# TRANSMITTER.net
KiCad netlist of a schematic drawn in Altium Designer
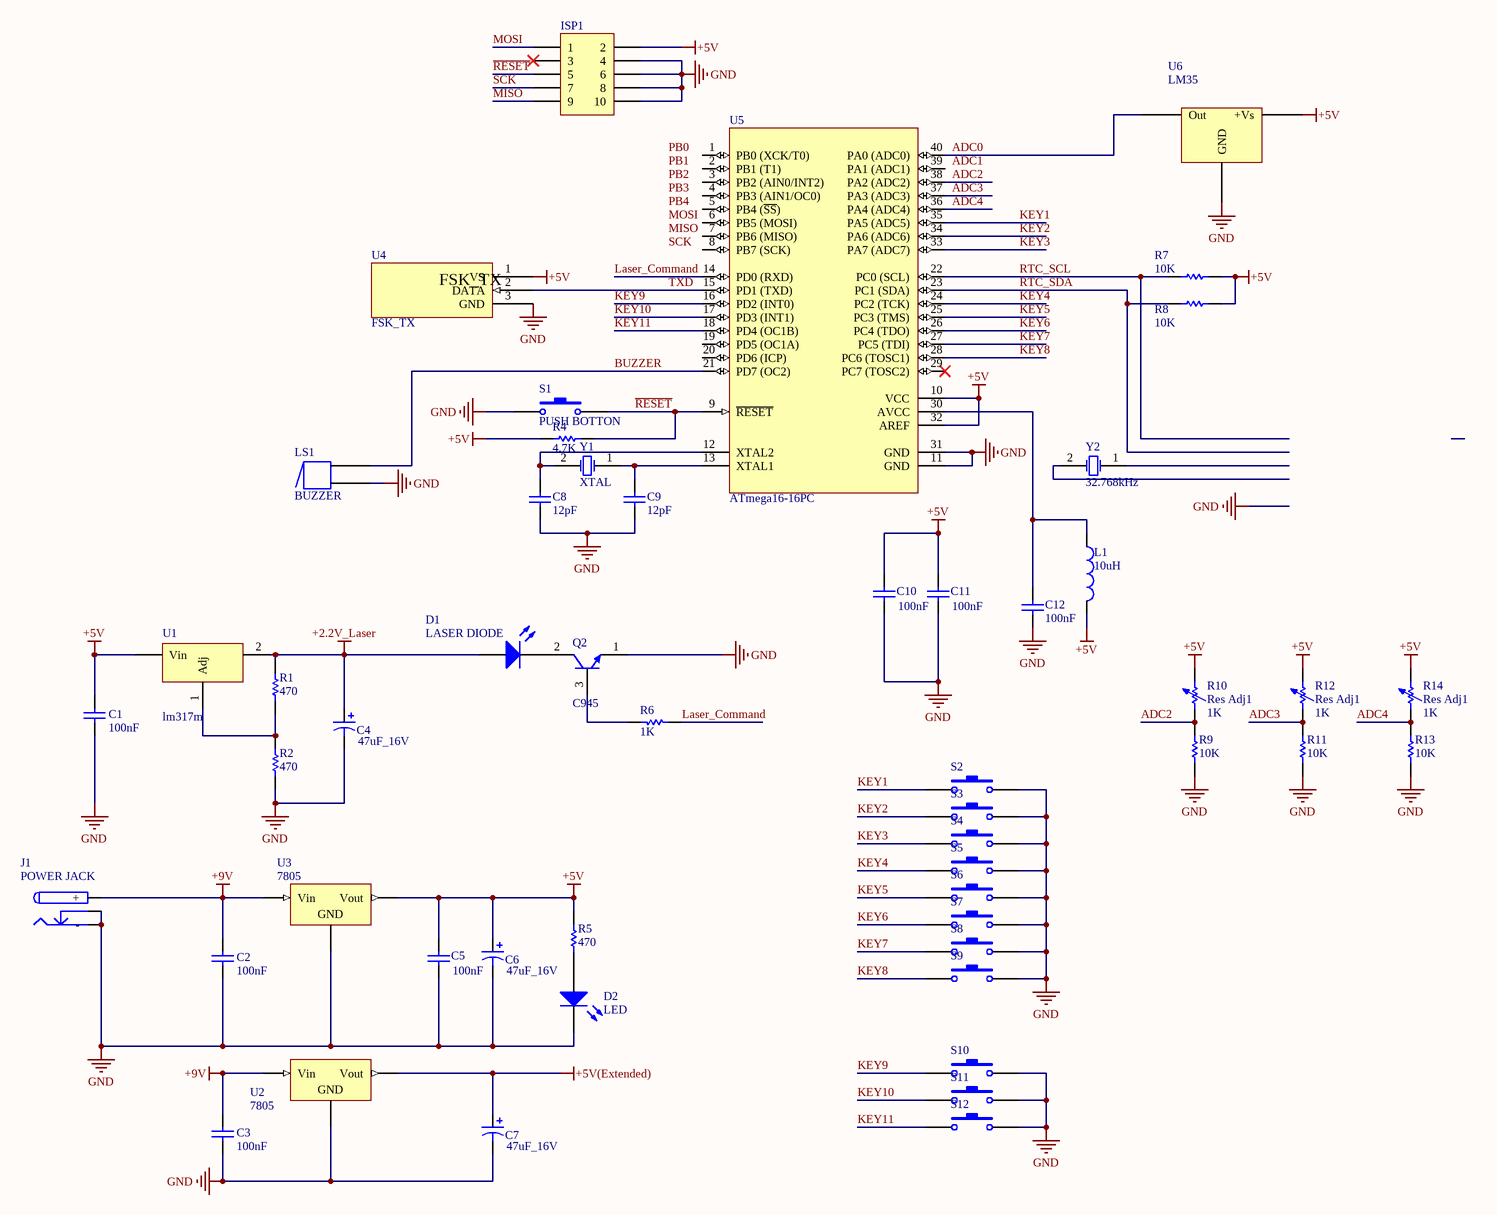
[diagram p0: TRANSMITTER.SchDoc]

(export (version "E")
  (design (tool "Eeschema 10.0.6"))
  (components
    (comp (ref "C1") (value "100nF") (footprint "BCY-W2/D3.1") (libsource (lib "SCHlib") (part "CAP")))
    (comp (ref "C2") (value "100nF") (footprint "BCY-W2/D3.1") (libsource (lib "SCHlib") (part "CAP")))
    (comp (ref "C3") (value "100nF") (footprint "BCY-W2/D3.1") (libsource (lib "SCHlib") (part "CAP")))
    (comp (ref "C4")
      (value "47uF_16V")
      (footprint "cap_pol")
      (fields (field (name "Comment") "CAP_POL"))
      (libsource (lib "SCHlib") (part "CAP_POL"))
    )
    (comp (ref "C5") (value "100nF") (footprint "BCY-W2/D3.1") (libsource (lib "SCHlib") (part "CAP")))
    (comp (ref "C6")
      (value "47uF_16V")
      (footprint "cap_pol")
      (fields (field (name "Comment") "CAP_POL"))
      (libsource (lib "SCHlib") (part "CAP_POL"))
    )
    (comp (ref "C7")
      (value "47uF_16V")
      (footprint "cap_pol")
      (fields (field (name "Comment") "CAP_POL"))
      (libsource (lib "SCHlib") (part "CAP_POL"))
    )
    (comp (ref "C8") (value "12pF") (footprint "BCY-W2/D3.1") (libsource (lib "SCHlib") (part "CAP")))
    (comp (ref "C9") (value "12pF") (footprint "BCY-W2/D3.1") (libsource (lib "SCHlib") (part "CAP")))
    (comp (ref "C10") (value "100nF") (footprint "BCY-W2/D3.1") (libsource (lib "SCHlib") (part "CAP")))
    (comp (ref "C11") (value "100nF") (footprint "BCY-W2/D3.1") (libsource (lib "SCHlib") (part "CAP")))
    (comp (ref "C12")
      (value "100nF")
      (footprint "BCY-W2/D3.1")
      (description "Capacitor (Semiconductor SIM Model)")
      (fields (field (name "PUBLISHER") "Altium Limited"))
      (libsource (lib "Miscellaneous Devices") (part "Cap Semi"))
    )
    (comp (ref "D1") (value "LASER DIODE") (footprint "Com_2pin") (libsource (lib "SCHlib") (part "LED")))
    (comp (ref "D2") (value "LED") (footprint "LED_3mm") (libsource (lib "SCHlib") (part "LED")))
    (comp (ref "ISP1")
      (value "ISP Programmer")
      (footprint "IDC2*5")
      (description "Header, 5-Pin, Dual row")
      (fields (field (name "PUBLISHER") "Altium Limited"))
      (libsource (lib "Miscellaneous Connectors") (part "Header 5X2"))
    )
    (comp (ref "J1") (value "POWER JACK") (footprint "term2") (libsource (lib "SCHlib") (part "POWER JACK")))
    (comp (ref "L1")
      (value "10uH")
      (footprint "AXIAL0.3")
      (description "Inductor")
      (fields (field (name "PUBLISHER") "Altium Limited"))
      (libsource (lib "SCH_lib") (part "Inductor"))
    )
    (comp (ref "LS1")
      (value "BUZZER")
      (footprint "buzzer")
      (description "Magnetic Transducer Buzzer")
      (libsource (lib "SCHlib") (part "BUZZER"))
    )
    (comp (ref "Q2")
      (value "C945")
      (footprint "C945")
      (description "NPN Bipolar Junction Transistor")
      (libsource (lib "SCHlib") (part "C945"))
    )
    (comp (ref "R1") (value "470") (footprint "AXIAL0.4") (libsource (lib "SCHlib") (part "RES")))
    (comp (ref "R2") (value "470") (footprint "AXIAL0.4") (libsource (lib "SCHlib") (part "RES")))
    (comp (ref "R4") (value "4.7K") (footprint "AXIAL0.4") (libsource (lib "SCHlib") (part "RES")))
    (comp (ref "R5") (value "470") (footprint "AXIAL0.4") (libsource (lib "SCHlib") (part "RES")))
    (comp (ref "R6") (value "1K") (footprint "AXIAL0.4") (libsource (lib "") (part "RES_1")))
    (comp (ref "R7") (value "10K") (footprint "AXIAL0.4") (libsource (lib "SCHlib") (part "RES")))
    (comp (ref "R8") (value "10K") (footprint "AXIAL0.4") (libsource (lib "SCHlib") (part "RES")))
    (comp (ref "R9") (value "10K") (footprint "AXIAL0.4") (libsource (lib "SCHlib") (part "RES")))
    (comp (ref "R10")
      (value "Res Adj1")
      (footprint "Com_2pin")
      (description "Variable Resistor")
      (fields (field (name "ALTIUM_VALUE") "1K") (field (name "PUBLISHER") "Altium Limited"))
      (libsource (lib "Miscellaneous Devices") (part "Res Adj1"))
    )
    (comp (ref "R11") (value "10K") (footprint "AXIAL0.4") (libsource (lib "SCHlib") (part "RES")))
    (comp (ref "R12")
      (value "Res Adj1")
      (footprint "Com_2pin")
      (description "Variable Resistor")
      (fields (field (name "ALTIUM_VALUE") "1K") (field (name "PUBLISHER") "Altium Limited"))
      (libsource (lib "Miscellaneous Devices") (part "Res Adj1"))
    )
    (comp (ref "R13") (value "10K") (footprint "AXIAL0.4") (libsource (lib "SCHlib") (part "RES")))
    (comp (ref "R14")
      (value "Res Adj1")
      (footprint "Com_2pin")
      (description "Variable Resistor")
      (fields (field (name "ALTIUM_VALUE") "1K") (field (name "PUBLISHER") "Altium Limited"))
      (libsource (lib "Miscellaneous Devices") (part "Res Adj1"))
    )
    (comp (ref "S1")
      (value "PUSH BOTTON")
      (footprint "PUSH BUTTON")
      (libsource (lib "SCHlib") (part "PUSH BOTTON"))
    )
    (comp (ref "S2")
      (value "PUSH BOTTON")
      (footprint "PUSH BUTTON")
      (libsource (lib "SCHlib") (part "PUSH BOTTON"))
    )
    (comp (ref "S3")
      (value "PUSH BOTTON")
      (footprint "PUSH BUTTON")
      (libsource (lib "SCHlib") (part "PUSH BOTTON"))
    )
    (comp (ref "S4")
      (value "PUSH BOTTON")
      (footprint "PUSH BUTTON")
      (libsource (lib "SCHlib") (part "PUSH BOTTON"))
    )
    (comp (ref "S5")
      (value "PUSH BOTTON")
      (footprint "PUSH BUTTON")
      (libsource (lib "SCHlib") (part "PUSH BOTTON"))
    )
    (comp (ref "S6")
      (value "PUSH BOTTON")
      (footprint "PUSH BUTTON")
      (libsource (lib "SCHlib") (part "PUSH BOTTON"))
    )
    (comp (ref "S7")
      (value "PUSH BOTTON")
      (footprint "PUSH BUTTON")
      (libsource (lib "SCHlib") (part "PUSH BOTTON"))
    )
    (comp (ref "S8")
      (value "PUSH BOTTON")
      (footprint "PUSH BUTTON")
      (libsource (lib "SCHlib") (part "PUSH BOTTON"))
    )
    (comp (ref "S9")
      (value "PUSH BOTTON")
      (footprint "PUSH BUTTON")
      (libsource (lib "SCHlib") (part "PUSH BOTTON"))
    )
    (comp (ref "S10")
      (value "PUSH BOTTON")
      (footprint "PUSH BUTTON")
      (libsource (lib "SCHlib") (part "PUSH BOTTON"))
    )
    (comp (ref "S11")
      (value "PUSH BOTTON")
      (footprint "PUSH BUTTON")
      (libsource (lib "SCHlib") (part "PUSH BOTTON"))
    )
    (comp (ref "S12")
      (value "PUSH BOTTON")
      (footprint "PUSH BUTTON")
      (libsource (lib "SCHlib") (part "PUSH BOTTON"))
    )
    (comp (ref "U1") (value "lm317m") (footprint "17D") (libsource (lib "RobotComponents") (part "lm317m")))
    (comp (ref "U2") (value "7805") (footprint "7805") (libsource (lib "SCHlib") (part "7805")))
    (comp (ref "U3") (value "7805") (footprint "7805") (libsource (lib "SCHlib") (part "7805")))
    (comp (ref "U4") (value "FSK_TX") (footprint "FSK_TX") (libsource (lib "SCHlib") (part "FSK_TX")))
    (comp (ref "U5")
      (value "ATmega16-16PC")
      (footprint "40P6")
      (description "8-Bit AVR Microcontroller with 16K Bytes of In-System Programmable Flash Memory")
      (fields (field (name "PUBLISHER") "Altium Limited"))
      (libsource (lib "SCHlib") (part "ATmega16-16PC"))
    )
    (comp (ref "U6") (value "LM35") (footprint "C945") (libsource (lib "RobotComponents") (part "LM35")))
    (comp (ref "Y1")
      (value "XTAL")
      (footprint "XTAL")
      (description "Crystal Oscillator")
      (fields (field (name "PUBLISHER") "Altium Limited"))
      (libsource (lib "SCHlib") (part "XTAL"))
    )
    (comp (ref "Y2")
      (value "32.768kHz")
      (footprint "R145")
      (description "Crystal Oscillator")
      (fields (field (name "PUBLISHER") "Altium Limited"))
      (libsource (lib "Miscellaneous Devices") (part "XTAL"))
    )
  )
  (nets
    (net (code "1") (name "+2.2V_Laser") (class "Default")
      (node (ref "C4") (pin "1") (pinfunction "1_1") (pintype "passive"))
      (node (ref "D1") (pin "1") (pinfunction "A_1") (pintype "passive"))
      (node (ref "R1") (pin "1") (pinfunction "1_1") (pintype "passive"))
      (node (ref "U1") (pin "2") (pinfunction "Vout_2") (pintype "passive"))
    )
    (net (code "2") (name "+5V") (class "Default")
      (node (ref "C1") (pin "2") (pinfunction "2_2") (pintype "passive"))
      (node (ref "C10") (pin "2") (pinfunction "2_2") (pintype "passive"))
      (node (ref "C11") (pin "2") (pinfunction "2_2") (pintype "passive"))
      (node (ref "C5") (pin "2") (pinfunction "2_2") (pintype "passive"))
      (node (ref "C6") (pin "1") (pinfunction "1_1") (pintype "passive"))
      (node (ref "ISP1") (pin "2") (pinfunction "2_2") (pintype "passive"))
      (node (ref "L1") (pin "2") (pinfunction "2_2") (pintype "passive"))
      (node (ref "R10") (pin "2") (pinfunction "2_2") (pintype "passive"))
      (node (ref "R12") (pin "2") (pinfunction "2_2") (pintype "passive"))
      (node (ref "R14") (pin "2") (pinfunction "2_2") (pintype "passive"))
      (node (ref "R4") (pin "2") (pinfunction "2_2") (pintype "passive"))
      (node (ref "R5") (pin "1") (pinfunction "1_1") (pintype "passive"))
      (node (ref "R7") (pin "2") (pinfunction "2_2") (pintype "passive"))
      (node (ref "R8") (pin "1") (pinfunction "1_1") (pintype "passive"))
      (node (ref "U1") (pin "3") (pinfunction "Vin_3") (pintype "passive"))
      (node (ref "U3") (pin "3") (pinfunction "Vout_3") (pintype "output"))
      (node (ref "U4") (pin "1") (pinfunction "VS_1") (pintype "power_in"))
      (node (ref "U5") (pin "10") (pinfunction "VCC_10") (pintype "power_in"))
      (node (ref "U5") (pin "32") (pinfunction "AREF_32") (pintype "passive"))
      (node (ref "U6") (pin "1") (pinfunction "+Vs_1") (pintype "passive"))
    )
    (net (code "3") (name "+5V(Extended)") (class "Default")
      (node (ref "C7") (pin "1") (pinfunction "1_1") (pintype "passive"))
      (node (ref "U2") (pin "3") (pinfunction "Vout_3") (pintype "output"))
    )
    (net (code "4") (name "+9V") (class "Default")
      (node (ref "C2") (pin "2") (pinfunction "2_2") (pintype "passive"))
      (node (ref "C3") (pin "2") (pinfunction "2_2") (pintype "passive"))
      (node (ref "J1") (pin "1") (pinfunction "+_1") (pintype "power_in"))
      (node (ref "U2") (pin "1") (pinfunction "Vin_1") (pintype "input"))
      (node (ref "U3") (pin "1") (pinfunction "Vin_1") (pintype "input"))
    )
    (net (code "5") (name "/ADC0") (class "Default")
      (node (ref "U5") (pin "40") (pinfunction "PA0_(ADC0)_40") (pintype "bidirectional"))
      (node (ref "U6") (pin "2") (pinfunction "Out_2") (pintype "passive"))
    )
    (net (code "7") (name "/ADC2") (class "Default")
      (node (ref "R10") (pin "1") (pinfunction "1_1") (pintype "passive"))
      (node (ref "R9") (pin "2") (pinfunction "2_2") (pintype "passive"))
      (node (ref "U5") (pin "38") (pinfunction "PA2_(ADC2)_38") (pintype "bidirectional"))
    )
    (net (code "8") (name "/ADC3") (class "Default")
      (node (ref "R11") (pin "2") (pinfunction "2_2") (pintype "passive"))
      (node (ref "R12") (pin "1") (pinfunction "1_1") (pintype "passive"))
      (node (ref "U5") (pin "37") (pinfunction "PA3_(ADC3)_37") (pintype "bidirectional"))
    )
    (net (code "9") (name "/ADC4") (class "Default")
      (node (ref "R13") (pin "2") (pinfunction "2_2") (pintype "passive"))
      (node (ref "R14") (pin "1") (pinfunction "1_1") (pintype "passive"))
      (node (ref "U5") (pin "36") (pinfunction "PA4_(ADC4)_36") (pintype "bidirectional"))
    )
    (net (code "10") (name "/BUZZER") (class "Default")
      (node (ref "LS1") (pin "1") (pinfunction "1_1") (pintype "passive"))
      (node (ref "U5") (pin "21") (pinfunction "PD7_(OC2)_21") (pintype "bidirectional"))
    )
    (net (code "11") (name "/KEY1") (class "Default")
      (node (ref "S2") (pin "1") (pinfunction "1_1") (pintype "passive"))
      (node (ref "U5") (pin "35") (pinfunction "PA5_(ADC5)_35") (pintype "bidirectional"))
    )
    (net (code "12") (name "/KEY2") (class "Default")
      (node (ref "S3") (pin "1") (pinfunction "1_1") (pintype "passive"))
      (node (ref "U5") (pin "34") (pinfunction "PA6_(ADC6)_34") (pintype "bidirectional"))
    )
    (net (code "13") (name "/KEY3") (class "Default")
      (node (ref "S4") (pin "1") (pinfunction "1_1") (pintype "passive"))
      (node (ref "U5") (pin "33") (pinfunction "PA7_(ADC7)_33") (pintype "bidirectional"))
    )
    (net (code "14") (name "/KEY4") (class "Default")
      (node (ref "S5") (pin "1") (pinfunction "1_1") (pintype "passive"))
      (node (ref "U5") (pin "24") (pinfunction "PC2_(TCK)_24") (pintype "bidirectional"))
    )
    (net (code "15") (name "/KEY5") (class "Default")
      (node (ref "S6") (pin "1") (pinfunction "1_1") (pintype "passive"))
      (node (ref "U5") (pin "25") (pinfunction "PC3_(TMS)_25") (pintype "bidirectional"))
    )
    (net (code "16") (name "/KEY6") (class "Default")
      (node (ref "S7") (pin "1") (pinfunction "1_1") (pintype "passive"))
      (node (ref "U5") (pin "26") (pinfunction "PC4_(TDO)_26") (pintype "bidirectional"))
    )
    (net (code "17") (name "/KEY7") (class "Default")
      (node (ref "S8") (pin "1") (pinfunction "1_1") (pintype "passive"))
      (node (ref "U5") (pin "27") (pinfunction "PC5_(TDI)_27") (pintype "bidirectional"))
    )
    (net (code "18") (name "/KEY8") (class "Default")
      (node (ref "S9") (pin "1") (pinfunction "1_1") (pintype "passive"))
      (node (ref "U5") (pin "28") (pinfunction "PC6_(TOSC1)_28") (pintype "bidirectional"))
    )
    (net (code "19") (name "/KEY9") (class "Default")
      (node (ref "S10") (pin "1") (pinfunction "1_1") (pintype "passive"))
      (node (ref "U5") (pin "16") (pinfunction "PD2_(INT0)_16") (pintype "bidirectional"))
    )
    (net (code "20") (name "/KEY10") (class "Default")
      (node (ref "S11") (pin "1") (pinfunction "1_1") (pintype "passive"))
      (node (ref "U5") (pin "17") (pinfunction "PD3_(INT1)_17") (pintype "bidirectional"))
    )
    (net (code "21") (name "/KEY11") (class "Default")
      (node (ref "S12") (pin "1") (pinfunction "1_1") (pintype "passive"))
      (node (ref "U5") (pin "18") (pinfunction "PD4_(OC1B)_18") (pintype "bidirectional"))
    )
    (net (code "22") (name "/Laser_Command") (class "Default")
      (node (ref "R6") (pin "1") (pinfunction "1_1") (pintype "passive"))
      (node (ref "U5") (pin "14") (pinfunction "PD0_(RXD)_14") (pintype "bidirectional"))
    )
    (net (code "23") (name "/MISO") (class "Default")
      (node (ref "ISP1") (pin "9") (pinfunction "9_9") (pintype "passive"))
    )
    (net (code "24") (name "/MOSI") (class "Default")
      (node (ref "ISP1") (pin "1") (pinfunction "1_1") (pintype "passive"))
    )
    (net (code "30") (name "/RTC_SCL") (class "Default")
      (node (ref "R7") (pin "1") (pinfunction "1_1") (pintype "passive"))
      (node (ref "U5") (pin "22") (pinfunction "PC0_(SCL)_22") (pintype "bidirectional"))
    )
    (net (code "31") (name "/RTC_SDA") (class "Default")
      (node (ref "R8") (pin "2") (pinfunction "2_2") (pintype "passive"))
      (node (ref "U5") (pin "23") (pinfunction "PC1_(SDA)_23") (pintype "bidirectional"))
    )
    (net (code "32") (name "/SCK") (class "Default")
      (node (ref "ISP1") (pin "7") (pinfunction "7_7") (pintype "passive"))
    )
    (net (code "33") (name "/TXD") (class "Default")
      (node (ref "U4") (pin "2") (pinfunction "DATA_2") (pintype "input"))
      (node (ref "U5") (pin "15") (pinfunction "PD1_(TXD)_15") (pintype "bidirectional"))
    )
    (net (code "34") (name "/~{RESET}") (class "Default")
      (node (ref "ISP1") (pin "5") (pinfunction "5_5") (pintype "passive"))
      (node (ref "R4") (pin "1") (pinfunction "1_1") (pintype "passive"))
      (node (ref "S1") (pin "2") (pinfunction "2_2") (pintype "passive"))
      (node (ref "U5") (pin "9") (pinfunction "~{RESET}_9") (pintype "input"))
    )
    (net (code "35") (name "GND") (class "Default")
      (node (ref "C1") (pin "1") (pinfunction "1_1") (pintype "passive"))
      (node (ref "C10") (pin "1") (pinfunction "1_1") (pintype "passive"))
      (node (ref "C11") (pin "1") (pinfunction "1_1") (pintype "passive"))
      (node (ref "C12") (pin "1") (pinfunction "1_1") (pintype "passive"))
      (node (ref "C2") (pin "1") (pinfunction "1_1") (pintype "passive"))
      (node (ref "C3") (pin "1") (pinfunction "1_1") (pintype "passive"))
      (node (ref "C4") (pin "2") (pinfunction "2_2") (pintype "passive"))
      (node (ref "C5") (pin "1") (pinfunction "1_1") (pintype "passive"))
      (node (ref "C6") (pin "2") (pinfunction "2_2") (pintype "passive"))
      (node (ref "C7") (pin "2") (pinfunction "2_2") (pintype "passive"))
      (node (ref "C8") (pin "1") (pinfunction "1_1") (pintype "passive"))
      (node (ref "C9") (pin "1") (pinfunction "1_1") (pintype "passive"))
      (node (ref "D2") (pin "2") (pinfunction "K_2") (pintype "passive"))
      (node (ref "ISP1") (pin "10") (pinfunction "10_10") (pintype "passive"))
      (node (ref "ISP1") (pin "4") (pinfunction "4_4") (pintype "passive"))
      (node (ref "ISP1") (pin "6") (pinfunction "6_6") (pintype "passive"))
      (node (ref "ISP1") (pin "8") (pinfunction "8_8") (pintype "passive"))
      (node (ref "J1") (pin "2") (pinfunction "-_2") (pintype "power_in"))
      (node (ref "LS1") (pin "2") (pinfunction "2_2") (pintype "passive"))
      (node (ref "Q2") (pin "1") (pinfunction "E_1") (pintype "passive"))
      (node (ref "R11") (pin "1") (pinfunction "1_1") (pintype "passive"))
      (node (ref "R13") (pin "1") (pinfunction "1_1") (pintype "passive"))
      (node (ref "R2") (pin "2") (pinfunction "2_2") (pintype "passive"))
      (node (ref "R9") (pin "1") (pinfunction "1_1") (pintype "passive"))
      (node (ref "S1") (pin "1") (pinfunction "1_1") (pintype "passive"))
      (node (ref "S10") (pin "2") (pinfunction "2_2") (pintype "passive"))
      (node (ref "S11") (pin "2") (pinfunction "2_2") (pintype "passive"))
      (node (ref "S12") (pin "2") (pinfunction "2_2") (pintype "passive"))
      (node (ref "S2") (pin "2") (pinfunction "2_2") (pintype "passive"))
      (node (ref "S3") (pin "2") (pinfunction "2_2") (pintype "passive"))
      (node (ref "S4") (pin "2") (pinfunction "2_2") (pintype "passive"))
      (node (ref "S5") (pin "2") (pinfunction "2_2") (pintype "passive"))
      (node (ref "S6") (pin "2") (pinfunction "2_2") (pintype "passive"))
      (node (ref "S7") (pin "2") (pinfunction "2_2") (pintype "passive"))
      (node (ref "S8") (pin "2") (pinfunction "2_2") (pintype "passive"))
      (node (ref "S9") (pin "2") (pinfunction "2_2") (pintype "passive"))
      (node (ref "U2") (pin "2") (pinfunction "GND_2") (pintype "power_in"))
      (node (ref "U3") (pin "2") (pinfunction "GND_2") (pintype "power_in"))
      (node (ref "U4") (pin "3") (pinfunction "GND_3") (pintype "power_in"))
      (node (ref "U5") (pin "11") (pinfunction "GND_11") (pintype "power_in"))
      (node (ref "U5") (pin "31") (pinfunction "GND_31") (pintype "power_in"))
      (node (ref "U6") (pin "3") (pinfunction "GND_3") (pintype "passive"))
    )
    (net (code "36") (name "Net-(D1-K)") (class "Default")
      (node (ref "D1") (pin "2") (pinfunction "K_2") (pintype "passive"))
      (node (ref "Q2") (pin "2") (pinfunction "C_2") (pintype "passive"))
    )
    (net (code "37") (name "Net-(D2-A)") (class "Default")
      (node (ref "D2") (pin "1") (pinfunction "A_1") (pintype "passive"))
      (node (ref "R5") (pin "2") (pinfunction "2_2") (pintype "passive"))
    )
    (net (code "38") (name "Net-(Q2-B)") (class "Default")
      (node (ref "Q2") (pin "3") (pinfunction "B_3") (pintype "passive"))
      (node (ref "R6") (pin "2") (pinfunction "2_2") (pintype "passive"))
    )
    (net (code "39") (name "Net-(U1-Adj)") (class "Default")
      (node (ref "R1") (pin "2") (pinfunction "2_2") (pintype "passive"))
      (node (ref "R2") (pin "1") (pinfunction "1_1") (pintype "passive"))
      (node (ref "U1") (pin "1") (pinfunction "Adj_1") (pintype "passive"))
    )
    (net (code "40") (name "Net-(U5-AVCC)") (class "Default")
      (node (ref "C12") (pin "2") (pinfunction "2_2") (pintype "passive"))
      (node (ref "L1") (pin "1") (pinfunction "1_1") (pintype "passive"))
      (node (ref "U5") (pin "30") (pinfunction "AVCC_30") (pintype "power_in"))
    )
    (net (code "41") (name "Net-(U5-XTAL1)") (class "Default")
      (node (ref "C9") (pin "2") (pinfunction "2_2") (pintype "passive"))
      (node (ref "U5") (pin "13") (pinfunction "XTAL1_13") (pintype "passive"))
      (node (ref "Y1") (pin "1") (pinfunction "OSC1_1") (pintype "passive"))
    )
    (net (code "42") (name "Net-(U5-XTAL2)") (class "Default")
      (node (ref "C8") (pin "2") (pinfunction "2_2") (pintype "passive"))
      (node (ref "U5") (pin "12") (pinfunction "XTAL2_12") (pintype "passive"))
      (node (ref "Y1") (pin "2") (pinfunction "OSC2_2") (pintype "passive"))
    )
    (net (code "43") (name "unconnected-(ISP1-Pad3)") (class "Default")
      (node (ref "ISP1") (pin "3") (pinfunction "3_3") (pintype "passive+no_connect"))
    )
    (net (code "44") (name "unconnected-(U5-PA1_(ADC1)-Pad39)") (class "Default")
      (node (ref "U5") (pin "39") (pinfunction "PA1_(ADC1)_39") (pintype "bidirectional"))
    )
    (net (code "45") (name "unconnected-(U5-PB0_(XCK{slash}T0)-Pad1)") (class "Default")
      (node (ref "U5") (pin "1") (pinfunction "PB0_(XCK/T0)_1") (pintype "bidirectional"))
    )
    (net (code "46") (name "unconnected-(U5-PB1_(T1)-Pad2)") (class "Default")
      (node (ref "U5") (pin "2") (pinfunction "PB1_(T1)_2") (pintype "bidirectional"))
    )
    (net (code "47") (name "unconnected-(U5-PB2_(AIN0{slash}INT2)-Pad3)") (class "Default")
      (node (ref "U5") (pin "3") (pinfunction "PB2_(AIN0/INT2)_3") (pintype "bidirectional"))
    )
    (net (code "48") (name "unconnected-(U5-PB3_(AIN1{slash}OC0)-Pad4)") (class "Default")
      (node (ref "U5") (pin "4") (pinfunction "PB3_(AIN1/OC0)_4") (pintype "bidirectional"))
    )
    (net (code "49") (name "unconnected-(U5-PB4_(~{SS})-Pad5)") (class "Default")
      (node (ref "U5") (pin "5") (pinfunction "PB4_(~{SS})_5") (pintype "bidirectional"))
    )
    (net (code "50") (name "unconnected-(U5-PB5_(MOSI)-Pad6)") (class "Default")
      (node (ref "U5") (pin "6") (pinfunction "PB5_(MOSI)_6") (pintype "bidirectional"))
    )
    (net (code "51") (name "unconnected-(U5-PB6_(MISO)-Pad7)") (class "Default")
      (node (ref "U5") (pin "7") (pinfunction "PB6_(MISO)_7") (pintype "bidirectional"))
    )
    (net (code "52") (name "unconnected-(U5-PB7_(SCK)-Pad8)") (class "Default")
      (node (ref "U5") (pin "8") (pinfunction "PB7_(SCK)_8") (pintype "bidirectional"))
    )
    (net (code "53") (name "unconnected-(U5-PC7_(TOSC2)-Pad29)") (class "Default")
      (node (ref "U5") (pin "29") (pinfunction "PC7_(TOSC2)_29") (pintype "bidirectional+no_connect"))
    )
    (net (code "54") (name "unconnected-(U5-PD5_(OC1A)-Pad19)") (class "Default")
      (node (ref "U5") (pin "19") (pinfunction "PD5_(OC1A)_19") (pintype "bidirectional"))
    )
    (net (code "55") (name "unconnected-(U5-PD6_(ICP)-Pad20)") (class "Default")
      (node (ref "U5") (pin "20") (pinfunction "PD6_(ICP)_20") (pintype "bidirectional"))
    )
    (net (code "56") (name "unconnected-(Y2-OSC1-Pad1)") (class "Default")
      (node (ref "Y2") (pin "1") (pinfunction "OSC1_1") (pintype "passive"))
    )
    (net (code "57") (name "unconnected-(Y2-OSC2-Pad2)") (class "Default")
      (node (ref "Y2") (pin "2") (pinfunction "OSC2_2") (pintype "passive"))
    )
  )
)
